# Sheet1.net
KiCad netlist of a schematic drawn in Altium Designer
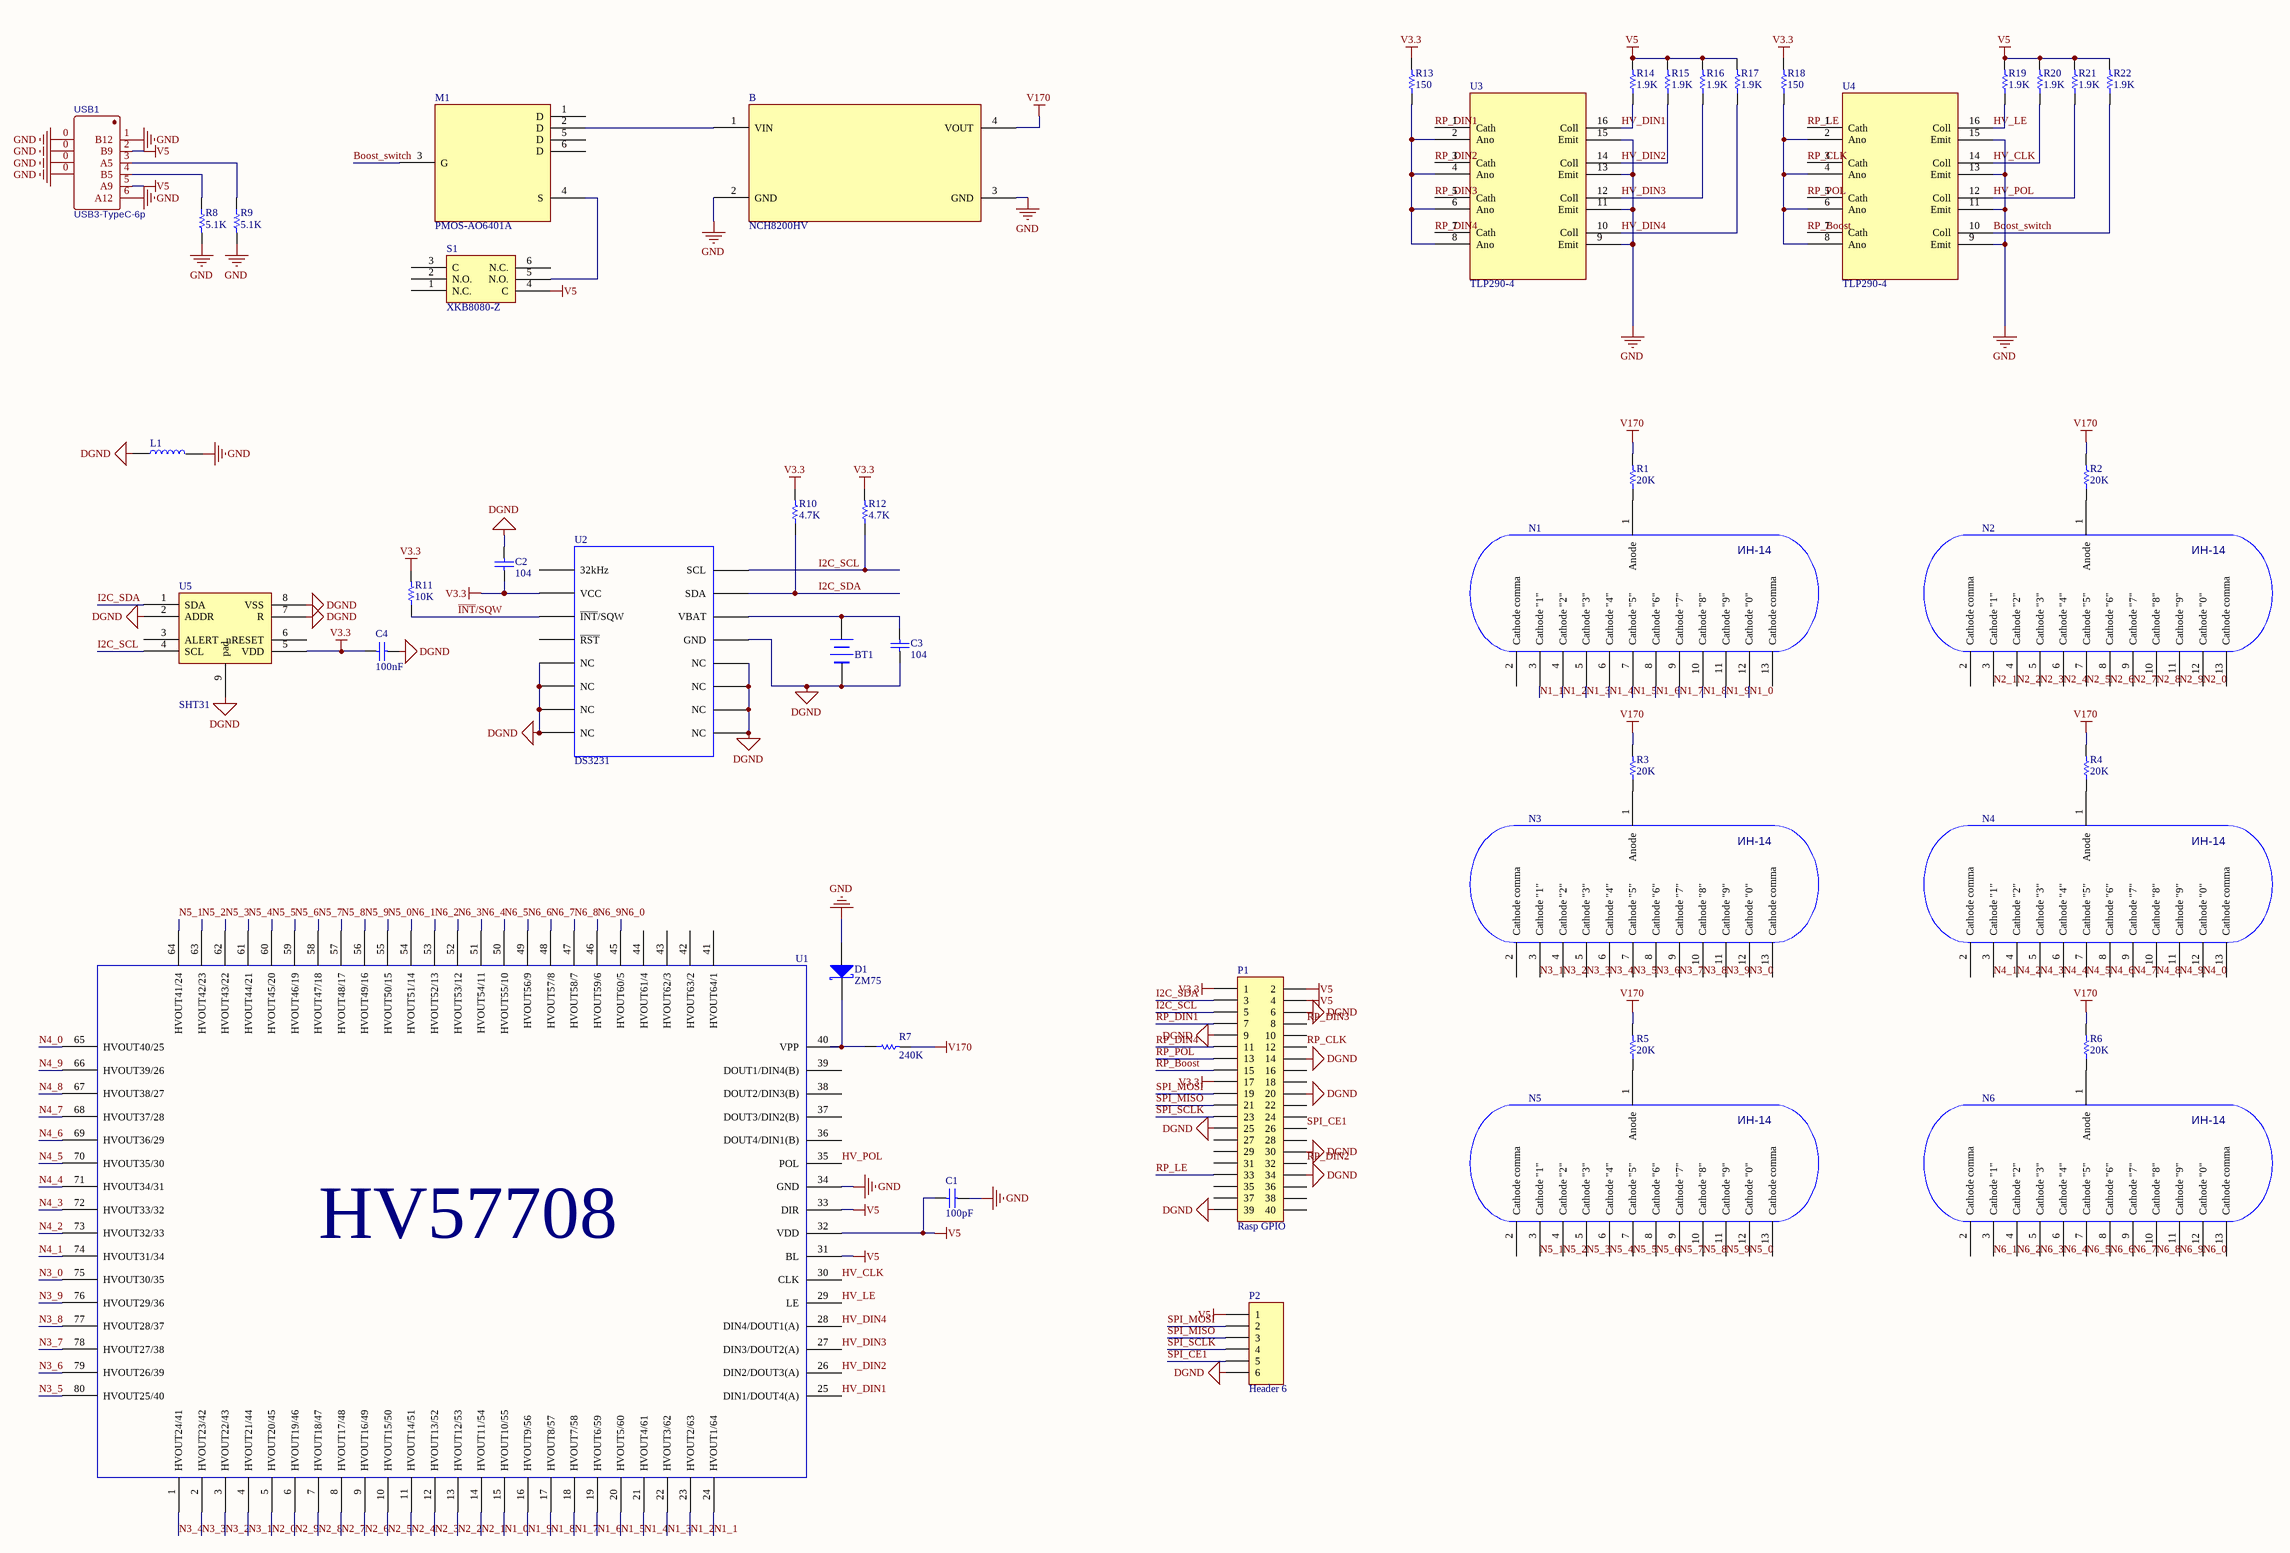
[diagram p0: Sheet1.SchDoc]

(export (version "E")
  (design (tool "Eeschema 10.0.6"))
  (components
    (comp (ref "B")
      (value "NCH8200HV")
      (footprint "NCH8200HV")
      (libsource (lib "Schlib1") (part "NCH8200HV"))
    )
    (comp (ref "BT1") (value "CR1220 holder") (footprint "BAT1220") (libsource (lib "何龙华") (part "BATTERY")))
    (comp (ref "C1")
      (value "100pF")
      (footprint "C0603")
      (description "Capacitor")
      (fields (field (name "Comment") "Cap") (field (name "PUBLISHER") "Altium Limited"))
      (libsource (lib "Miscellaneous Devices") (part "Cap"))
    )
    (comp (ref "C2")
      (value "104")
      (footprint "C0603")
      (description "Capacitor (Semiconductor SIM Model)")
      (fields (field (name "Comment") "Cap Semi") (field (name "PUBLISHER") "Altium Limited"))
      (libsource (lib "何龙华") (part "Cap Semi"))
    )
    (comp (ref "C3")
      (value "104")
      (footprint "C0603")
      (description "Capacitor (Semiconductor SIM Model)")
      (fields (field (name "Comment") "Cap Semi") (field (name "PUBLISHER") "Altium Limited"))
      (libsource (lib "何龙华") (part "Cap Semi"))
    )
    (comp (ref "C4")
      (value "100nF")
      (footprint "C0603")
      (description "Capacitor")
      (fields (field (name "Comment") "Cap") (field (name "PUBLISHER") "Altium Limited"))
      (libsource (lib "Miscellaneous Devices") (part "Cap"))
    )
    (comp (ref "D1")
      (value "ZM75")
      (footprint "LL-34")
      (description "Schottky Rectifier")
      (fields (field (name "PUBLISHER") "Altium Limited"))
      (libsource (lib "Miscellaneous Devices") (part "Diode 11DQ03"))
    )
    (comp (ref "L1") (value "L0") (footprint "0805") (libsource (lib "何龙华") (part "L0")))
    (comp (ref "M1")
      (value "PMOS-AO6401A")
      (footprint "SOT95P250X110-6N")
      (libsource (lib "Schlib1") (part "AO6401A"))
    )
    (comp (ref "N1") (value "ИН-14") (footprint "IN14") (libsource (lib "NIXIEClock_SCHLib") (part "ИН-14")))
    (comp (ref "N2") (value "ИН-14") (footprint "IN14") (libsource (lib "NIXIEClock_SCHLib") (part "ИН-14")))
    (comp (ref "N3") (value "ИН-14") (footprint "IN14") (libsource (lib "NIXIEClock_SCHLib") (part "ИН-14")))
    (comp (ref "N4") (value "ИН-14") (footprint "IN14") (libsource (lib "NIXIEClock_SCHLib") (part "ИН-14")))
    (comp (ref "N5") (value "ИН-14") (footprint "IN14") (libsource (lib "NIXIEClock_SCHLib") (part "ИН-14")))
    (comp (ref "N6") (value "ИН-14") (footprint "IN14") (libsource (lib "NIXIEClock_SCHLib") (part "ИН-14")))
    (comp (ref "P1")
      (value "Rasp GPIO")
      (footprint "HDR2.54-LI-2x20P")
      (description "Header, 20-Pin, Dual row")
      (fields (field (name "PUBLISHER") "Altium Limited"))
      (libsource (lib "Miscellaneous Connectors") (part "Header 20X2"))
    )
    (comp (ref "P2")
      (value "Header 6")
      (footprint "HDR2.54-LI-6P")
      (description "Header, 6-Pin")
      (fields (field (name "PUBLISHER") "Altium Limited"))
      (libsource (lib "Miscellaneous Connectors") (part "Header 6"))
    )
    (comp (ref "R1")
      (value "20K")
      (footprint "R0603")
      (description "Semiconductor Resistor")
      (fields (field (name "Comment") "Res Semi") (field (name "PUBLISHER") "Altium Limited"))
      (libsource (lib "何龙华") (part "Res Semi"))
    )
    (comp (ref "R2")
      (value "20K")
      (footprint "R0603")
      (description "Semiconductor Resistor")
      (fields (field (name "Comment") "Res Semi") (field (name "PUBLISHER") "Altium Limited"))
      (libsource (lib "何龙华") (part "Res Semi"))
    )
    (comp (ref "R3")
      (value "20K")
      (footprint "R0603")
      (description "Semiconductor Resistor")
      (fields (field (name "Comment") "Res Semi") (field (name "PUBLISHER") "Altium Limited"))
      (libsource (lib "何龙华") (part "Res Semi"))
    )
    (comp (ref "R4")
      (value "20K")
      (footprint "R0603")
      (description "Semiconductor Resistor")
      (fields (field (name "Comment") "Res Semi") (field (name "PUBLISHER") "Altium Limited"))
      (libsource (lib "何龙华") (part "Res Semi"))
    )
    (comp (ref "R5")
      (value "20K")
      (footprint "R0603")
      (description "Semiconductor Resistor")
      (fields (field (name "Comment") "Res Semi") (field (name "PUBLISHER") "Altium Limited"))
      (libsource (lib "何龙华") (part "Res Semi"))
    )
    (comp (ref "R6")
      (value "20K")
      (footprint "R0603")
      (description "Semiconductor Resistor")
      (fields (field (name "Comment") "Res Semi") (field (name "PUBLISHER") "Altium Limited"))
      (libsource (lib "何龙华") (part "Res Semi"))
    )
    (comp (ref "R7")
      (value "240K")
      (footprint "R0603")
      (description "Semiconductor Resistor")
      (fields (field (name "Comment") "Res Semi") (field (name "PUBLISHER") "Altium Limited"))
      (libsource (lib "何龙华") (part "Res Semi"))
    )
    (comp (ref "R8")
      (value "5.1K")
      (footprint "R0603")
      (description "Semiconductor Resistor")
      (fields (field (name "Comment") "Res Semi") (field (name "PUBLISHER") "Altium Limited"))
      (libsource (lib "何龙华") (part "Res Semi"))
    )
    (comp (ref "R9")
      (value "5.1K")
      (footprint "R0603")
      (description "Semiconductor Resistor")
      (fields (field (name "Comment") "Res Semi") (field (name "PUBLISHER") "Altium Limited"))
      (libsource (lib "何龙华") (part "Res Semi"))
    )
    (comp (ref "R10")
      (value "4.7K")
      (footprint "R0603")
      (description "Semiconductor Resistor")
      (fields (field (name "Comment") "Res Semi") (field (name "PUBLISHER") "Altium Limited"))
      (libsource (lib "何龙华") (part "Res Semi"))
    )
    (comp (ref "R11")
      (value "10K")
      (footprint "R0603")
      (description "Semiconductor Resistor")
      (fields (field (name "Comment") "Res Semi") (field (name "PUBLISHER") "Altium Limited"))
      (libsource (lib "何龙华") (part "Res Semi"))
    )
    (comp (ref "R12")
      (value "4.7K")
      (footprint "R0603")
      (description "Semiconductor Resistor")
      (fields (field (name "Comment") "Res Semi") (field (name "PUBLISHER") "Altium Limited"))
      (libsource (lib "何龙华") (part "Res Semi"))
    )
    (comp (ref "R13")
      (value "150")
      (footprint "R0603")
      (description "Semiconductor Resistor")
      (fields (field (name "Comment") "Res Semi") (field (name "PUBLISHER") "Altium Limited"))
      (libsource (lib "何龙华") (part "Res Semi"))
    )
    (comp (ref "R14")
      (value "1.9K")
      (footprint "R0603")
      (description "Semiconductor Resistor")
      (fields (field (name "Comment") "Res Semi") (field (name "PUBLISHER") "Altium Limited"))
      (libsource (lib "何龙华") (part "Res Semi"))
    )
    (comp (ref "R15")
      (value "1.9K")
      (footprint "R0603")
      (description "Semiconductor Resistor")
      (fields (field (name "Comment") "Res Semi") (field (name "PUBLISHER") "Altium Limited"))
      (libsource (lib "何龙华") (part "Res Semi"))
    )
    (comp (ref "R16")
      (value "1.9K")
      (footprint "R0603")
      (description "Semiconductor Resistor")
      (fields (field (name "Comment") "Res Semi") (field (name "PUBLISHER") "Altium Limited"))
      (libsource (lib "何龙华") (part "Res Semi"))
    )
    (comp (ref "R17")
      (value "1.9K")
      (footprint "R0603")
      (description "Semiconductor Resistor")
      (fields (field (name "Comment") "Res Semi") (field (name "PUBLISHER") "Altium Limited"))
      (libsource (lib "何龙华") (part "Res Semi"))
    )
    (comp (ref "R18")
      (value "150")
      (footprint "R0603")
      (description "Semiconductor Resistor")
      (fields (field (name "Comment") "Res Semi") (field (name "PUBLISHER") "Altium Limited"))
      (libsource (lib "何龙华") (part "Res Semi"))
    )
    (comp (ref "R19")
      (value "1.9K")
      (footprint "R0603")
      (description "Semiconductor Resistor")
      (fields (field (name "Comment") "Res Semi") (field (name "PUBLISHER") "Altium Limited"))
      (libsource (lib "何龙华") (part "Res Semi"))
    )
    (comp (ref "R20")
      (value "1.9K")
      (footprint "R0603")
      (description "Semiconductor Resistor")
      (fields (field (name "Comment") "Res Semi") (field (name "PUBLISHER") "Altium Limited"))
      (libsource (lib "何龙华") (part "Res Semi"))
    )
    (comp (ref "R21")
      (value "1.9K")
      (footprint "R0603")
      (description "Semiconductor Resistor")
      (fields (field (name "Comment") "Res Semi") (field (name "PUBLISHER") "Altium Limited"))
      (libsource (lib "何龙华") (part "Res Semi"))
    )
    (comp (ref "R22")
      (value "1.9K")
      (footprint "R0603")
      (description "Semiconductor Resistor")
      (fields (field (name "Comment") "Res Semi") (field (name "PUBLISHER") "Altium Limited"))
      (libsource (lib "何龙华") (part "Res Semi"))
    )
    (comp (ref "S1")
      (value "XKB8080-Z")
      (footprint "SW_PVA2EEH21.7NV2")
      (libsource (lib "Schlib1") (part "XKB8080-Z"))
    )
    (comp (ref "U1")
      (value "HV57708")
      (footprint "HV57708PG")
      (libsource (lib "NIXIEClock_SCHLib") (part "HV57708"))
    )
    (comp (ref "U2") (value "DS3231") (footprint "SOP16_75MM") (libsource (lib "NIXIEClock") (part "DS3231")))
    (comp (ref "U3") (value "TLP290-4") (footprint "SO16") (libsource (lib "Schlib1") (part "TLP290-4")))
    (comp (ref "U4") (value "TLP290-4") (footprint "SO16") (libsource (lib "Schlib1") (part "TLP290-4")))
    (comp (ref "U5") (value "SHT31") (footprint "SHT3x-x-P") (libsource (lib "Schlib1") (part "SHT31")))
    (comp (ref "USB1")
      (value "USB3-TypeC-6p")
      (footprint "USB-TYPE-C-SMD6")
      (libsource (lib "type-c-sch") (part "USB3-TypeC-6p"))
    )
  )
  (nets
    (net (code "1") (name "/Boost_switch") (class "Default")
      (node (ref "M1") (pin "3") (pinfunction "G_3") (pintype "passive"))
      (node (ref "R22") (pin "1") (pinfunction "1_1") (pintype "passive"))
      (node (ref "U4") (pin "10") (pinfunction "Coll_10") (pintype "passive"))
    )
    (net (code "2") (name "/HV_CLK") (class "Default")
      (node (ref "R20") (pin "1") (pinfunction "1_1") (pintype "passive"))
      (node (ref "U1") (pin "30") (pinfunction "CLK_30") (pintype "passive"))
      (node (ref "U4") (pin "14") (pinfunction "Coll_14") (pintype "passive"))
    )
    (net (code "3") (name "/HV_DIN1") (class "Default")
      (node (ref "R14") (pin "1") (pinfunction "1_1") (pintype "passive"))
      (node (ref "U1") (pin "25") (pinfunction "DIN1/DOUT4(A)_25") (pintype "passive"))
      (node (ref "U3") (pin "16") (pinfunction "Coll_16") (pintype "passive"))
    )
    (net (code "4") (name "/HV_DIN2") (class "Default")
      (node (ref "R15") (pin "1") (pinfunction "1_1") (pintype "passive"))
      (node (ref "U1") (pin "26") (pinfunction "DIN2/DOUT3(A)_26") (pintype "passive"))
      (node (ref "U3") (pin "14") (pinfunction "Coll_14") (pintype "passive"))
    )
    (net (code "5") (name "/HV_DIN3") (class "Default")
      (node (ref "R16") (pin "1") (pinfunction "1_1") (pintype "passive"))
      (node (ref "U1") (pin "27") (pinfunction "DIN3/DOUT2(A)_27") (pintype "passive"))
      (node (ref "U3") (pin "12") (pinfunction "Coll_12") (pintype "passive"))
    )
    (net (code "6") (name "/HV_DIN4") (class "Default")
      (node (ref "R17") (pin "1") (pinfunction "1_1") (pintype "passive"))
      (node (ref "U1") (pin "28") (pinfunction "DIN4/DOUT1(A)_28") (pintype "passive"))
      (node (ref "U3") (pin "10") (pinfunction "Coll_10") (pintype "passive"))
    )
    (net (code "7") (name "/HV_LE") (class "Default")
      (node (ref "R19") (pin "1") (pinfunction "1_1") (pintype "passive"))
      (node (ref "U1") (pin "29") (pinfunction "LE_29") (pintype "passive"))
      (node (ref "U4") (pin "16") (pinfunction "Coll_16") (pintype "passive"))
    )
    (net (code "8") (name "/HV_POL") (class "Default")
      (node (ref "R21") (pin "1") (pinfunction "1_1") (pintype "passive"))
      (node (ref "U1") (pin "35") (pinfunction "POL_35") (pintype "passive"))
      (node (ref "U4") (pin "12") (pinfunction "Coll_12") (pintype "passive"))
    )
    (net (code "9") (name "/I2C_SCL") (class "Default")
      (node (ref "P1") (pin "5") (pinfunction "5_5") (pintype "passive"))
      (node (ref "R12") (pin "1") (pinfunction "1_1") (pintype "passive"))
      (node (ref "U2") (pin "16") (pinfunction "SCL_16") (pintype "passive"))
      (node (ref "U5") (pin "4") (pinfunction "SCL_4") (pintype "passive"))
    )
    (net (code "10") (name "/I2C_SDA") (class "Default")
      (node (ref "P1") (pin "3") (pinfunction "3_3") (pintype "passive"))
      (node (ref "R10") (pin "1") (pinfunction "1_1") (pintype "passive"))
      (node (ref "U2") (pin "15") (pinfunction "SDA_15") (pintype "passive"))
      (node (ref "U5") (pin "1") (pinfunction "SDA_1") (pintype "passive"))
    )
    (net (code "11") (name "/N1_0") (class "Default")
      (node (ref "N1") (pin "12") (pinfunction "Cathode_\"0\"_12") (pintype "passive"))
      (node (ref "U1") (pin "15") (pinfunction "HVOUT10/55_15") (pintype "passive"))
    )
    (net (code "12") (name "/N1_1") (class "Default")
      (node (ref "N1") (pin "3") (pinfunction "Cathode_\"1\"_3") (pintype "passive"))
      (node (ref "U1") (pin "24") (pinfunction "HVOUT1/64_24") (pintype "passive"))
    )
    (net (code "13") (name "/N1_2") (class "Default")
      (node (ref "N1") (pin "4") (pinfunction "Cathode_\"2\"_4") (pintype "passive"))
      (node (ref "U1") (pin "23") (pinfunction "HVOUT2/63_23") (pintype "passive"))
    )
    (net (code "14") (name "/N1_3") (class "Default")
      (node (ref "N1") (pin "5") (pinfunction "Cathode_\"3\"_5") (pintype "passive"))
      (node (ref "U1") (pin "22") (pinfunction "HVOUT3/62_22") (pintype "passive"))
    )
    (net (code "15") (name "/N1_4") (class "Default")
      (node (ref "N1") (pin "6") (pinfunction "Cathode_\"4\"_6") (pintype "passive"))
      (node (ref "U1") (pin "21") (pinfunction "HVOUT4/61_21") (pintype "passive"))
    )
    (net (code "16") (name "/N1_5") (class "Default")
      (node (ref "N1") (pin "7") (pinfunction "Cathode_\"5\"_7") (pintype "passive"))
      (node (ref "U1") (pin "20") (pinfunction "HVOUT5/60_20") (pintype "passive"))
    )
    (net (code "17") (name "/N1_6") (class "Default")
      (node (ref "N1") (pin "8") (pinfunction "Cathode_\"6\"_8") (pintype "passive"))
      (node (ref "U1") (pin "19") (pinfunction "HVOUT6/59_19") (pintype "passive"))
    )
    (net (code "18") (name "/N1_7") (class "Default")
      (node (ref "N1") (pin "9") (pinfunction "Cathode_\"7\"_9") (pintype "passive"))
      (node (ref "U1") (pin "18") (pinfunction "HVOUT7/58_18") (pintype "passive"))
    )
    (net (code "19") (name "/N1_8") (class "Default")
      (node (ref "N1") (pin "10") (pinfunction "Cathode_\"8\"_10") (pintype "passive"))
      (node (ref "U1") (pin "17") (pinfunction "HVOUT8/57_17") (pintype "passive"))
    )
    (net (code "20") (name "/N1_9") (class "Default")
      (node (ref "N1") (pin "11") (pinfunction "Cathode_\"9\"_11") (pintype "passive"))
      (node (ref "U1") (pin "16") (pinfunction "HVOUT9/56_16") (pintype "passive"))
    )
    (net (code "21") (name "/N2_0") (class "Default")
      (node (ref "N2") (pin "12") (pinfunction "Cathode_\"0\"_12") (pintype "passive"))
      (node (ref "U1") (pin "5") (pinfunction "HVOUT20/45_5") (pintype "passive"))
    )
    (net (code "22") (name "/N2_1") (class "Default")
      (node (ref "N2") (pin "3") (pinfunction "Cathode_\"1\"_3") (pintype "passive"))
      (node (ref "U1") (pin "14") (pinfunction "HVOUT11/54_14") (pintype "passive"))
    )
    (net (code "23") (name "/N2_2") (class "Default")
      (node (ref "N2") (pin "4") (pinfunction "Cathode_\"2\"_4") (pintype "passive"))
      (node (ref "U1") (pin "13") (pinfunction "HVOUT12/53_13") (pintype "passive"))
    )
    (net (code "24") (name "/N2_3") (class "Default")
      (node (ref "N2") (pin "5") (pinfunction "Cathode_\"3\"_5") (pintype "passive"))
      (node (ref "U1") (pin "12") (pinfunction "HVOUT13/52_12") (pintype "passive"))
    )
    (net (code "25") (name "/N2_4") (class "Default")
      (node (ref "N2") (pin "6") (pinfunction "Cathode_\"4\"_6") (pintype "passive"))
      (node (ref "U1") (pin "11") (pinfunction "HVOUT14/51_11") (pintype "passive"))
    )
    (net (code "26") (name "/N2_5") (class "Default")
      (node (ref "N2") (pin "7") (pinfunction "Cathode_\"5\"_7") (pintype "passive"))
      (node (ref "U1") (pin "10") (pinfunction "HVOUT15/50_10") (pintype "passive"))
    )
    (net (code "27") (name "/N2_6") (class "Default")
      (node (ref "N2") (pin "8") (pinfunction "Cathode_\"6\"_8") (pintype "passive"))
      (node (ref "U1") (pin "9") (pinfunction "HVOUT16/49_9") (pintype "passive"))
    )
    (net (code "28") (name "/N2_7") (class "Default")
      (node (ref "N2") (pin "9") (pinfunction "Cathode_\"7\"_9") (pintype "passive"))
      (node (ref "U1") (pin "8") (pinfunction "HVOUT17/48_8") (pintype "passive"))
    )
    (net (code "29") (name "/N2_8") (class "Default")
      (node (ref "N2") (pin "10") (pinfunction "Cathode_\"8\"_10") (pintype "passive"))
      (node (ref "U1") (pin "7") (pinfunction "HVOUT18/47_7") (pintype "passive"))
    )
    (net (code "30") (name "/N2_9") (class "Default")
      (node (ref "N2") (pin "11") (pinfunction "Cathode_\"9\"_11") (pintype "passive"))
      (node (ref "U1") (pin "6") (pinfunction "HVOUT19/46_6") (pintype "passive"))
    )
    (net (code "31") (name "/N3_0") (class "Default")
      (node (ref "N3") (pin "12") (pinfunction "Cathode_\"0\"_12") (pintype "passive"))
      (node (ref "U1") (pin "75") (pinfunction "HVOUT30/35_75") (pintype "passive"))
    )
    (net (code "32") (name "/N3_1") (class "Default")
      (node (ref "N3") (pin "3") (pinfunction "Cathode_\"1\"_3") (pintype "passive"))
      (node (ref "U1") (pin "4") (pinfunction "HVOUT21/44_4") (pintype "passive"))
    )
    (net (code "33") (name "/N3_2") (class "Default")
      (node (ref "N3") (pin "4") (pinfunction "Cathode_\"2\"_4") (pintype "passive"))
      (node (ref "U1") (pin "3") (pinfunction "HVOUT22/43_3") (pintype "passive"))
    )
    (net (code "34") (name "/N3_3") (class "Default")
      (node (ref "N3") (pin "5") (pinfunction "Cathode_\"3\"_5") (pintype "passive"))
      (node (ref "U1") (pin "2") (pinfunction "HVOUT23/42_2") (pintype "passive"))
    )
    (net (code "35") (name "/N3_4") (class "Default")
      (node (ref "N3") (pin "6") (pinfunction "Cathode_\"4\"_6") (pintype "passive"))
      (node (ref "U1") (pin "1") (pinfunction "HVOUT24/41_1") (pintype "passive"))
    )
    (net (code "36") (name "/N3_5") (class "Default")
      (node (ref "N3") (pin "7") (pinfunction "Cathode_\"5\"_7") (pintype "passive"))
      (node (ref "U1") (pin "80") (pinfunction "HVOUT25/40_80") (pintype "passive"))
    )
    (net (code "37") (name "/N3_6") (class "Default")
      (node (ref "N3") (pin "8") (pinfunction "Cathode_\"6\"_8") (pintype "passive"))
      (node (ref "U1") (pin "79") (pinfunction "HVOUT26/39_79") (pintype "passive"))
    )
    (net (code "38") (name "/N3_7") (class "Default")
      (node (ref "N3") (pin "9") (pinfunction "Cathode_\"7\"_9") (pintype "passive"))
      (node (ref "U1") (pin "78") (pinfunction "HVOUT27/38_78") (pintype "passive"))
    )
    (net (code "39") (name "/N3_8") (class "Default")
      (node (ref "N3") (pin "10") (pinfunction "Cathode_\"8\"_10") (pintype "passive"))
      (node (ref "U1") (pin "77") (pinfunction "HVOUT28/37_77") (pintype "passive"))
    )
    (net (code "40") (name "/N3_9") (class "Default")
      (node (ref "N3") (pin "11") (pinfunction "Cathode_\"9\"_11") (pintype "passive"))
      (node (ref "U1") (pin "76") (pinfunction "HVOUT29/36_76") (pintype "passive"))
    )
    (net (code "41") (name "/N4_0") (class "Default")
      (node (ref "N4") (pin "12") (pinfunction "Cathode_\"0\"_12") (pintype "passive"))
      (node (ref "U1") (pin "65") (pinfunction "HVOUT40/25_65") (pintype "passive"))
    )
    (net (code "42") (name "/N4_1") (class "Default")
      (node (ref "N4") (pin "3") (pinfunction "Cathode_\"1\"_3") (pintype "passive"))
      (node (ref "U1") (pin "74") (pinfunction "HVOUT31/34_74") (pintype "passive"))
    )
    (net (code "43") (name "/N4_2") (class "Default")
      (node (ref "N4") (pin "4") (pinfunction "Cathode_\"2\"_4") (pintype "passive"))
      (node (ref "U1") (pin "73") (pinfunction "HVOUT32/33_73") (pintype "passive"))
    )
    (net (code "44") (name "/N4_3") (class "Default")
      (node (ref "N4") (pin "5") (pinfunction "Cathode_\"3\"_5") (pintype "passive"))
      (node (ref "U1") (pin "72") (pinfunction "HVOUT33/32_72") (pintype "passive"))
    )
    (net (code "45") (name "/N4_4") (class "Default")
      (node (ref "N4") (pin "6") (pinfunction "Cathode_\"4\"_6") (pintype "passive"))
      (node (ref "U1") (pin "71") (pinfunction "HVOUT34/31_71") (pintype "passive"))
    )
    (net (code "46") (name "/N4_5") (class "Default")
      (node (ref "N4") (pin "7") (pinfunction "Cathode_\"5\"_7") (pintype "passive"))
      (node (ref "U1") (pin "70") (pinfunction "HVOUT35/30_70") (pintype "passive"))
    )
    (net (code "47") (name "/N4_6") (class "Default")
      (node (ref "N4") (pin "8") (pinfunction "Cathode_\"6\"_8") (pintype "passive"))
      (node (ref "U1") (pin "69") (pinfunction "HVOUT36/29_69") (pintype "passive"))
    )
    (net (code "48") (name "/N4_7") (class "Default")
      (node (ref "N4") (pin "9") (pinfunction "Cathode_\"7\"_9") (pintype "passive"))
      (node (ref "U1") (pin "68") (pinfunction "HVOUT37/28_68") (pintype "passive"))
    )
    (net (code "49") (name "/N4_8") (class "Default")
      (node (ref "N4") (pin "10") (pinfunction "Cathode_\"8\"_10") (pintype "passive"))
      (node (ref "U1") (pin "67") (pinfunction "HVOUT38/27_67") (pintype "passive"))
    )
    (net (code "50") (name "/N4_9") (class "Default")
      (node (ref "N4") (pin "11") (pinfunction "Cathode_\"9\"_11") (pintype "passive"))
      (node (ref "U1") (pin "66") (pinfunction "HVOUT39/26_66") (pintype "passive"))
    )
    (net (code "51") (name "/N5_0") (class "Default")
      (node (ref "N5") (pin "12") (pinfunction "Cathode_\"0\"_12") (pintype "passive"))
      (node (ref "U1") (pin "55") (pinfunction "HVOUT50/15_55") (pintype "passive"))
    )
    (net (code "52") (name "/N5_1") (class "Default")
      (node (ref "N5") (pin "3") (pinfunction "Cathode_\"1\"_3") (pintype "passive"))
      (node (ref "U1") (pin "64") (pinfunction "HVOUT41/24_64") (pintype "passive"))
    )
    (net (code "53") (name "/N5_2") (class "Default")
      (node (ref "N5") (pin "4") (pinfunction "Cathode_\"2\"_4") (pintype "passive"))
      (node (ref "U1") (pin "63") (pinfunction "HVOUT42/23_63") (pintype "passive"))
    )
    (net (code "54") (name "/N5_3") (class "Default")
      (node (ref "N5") (pin "5") (pinfunction "Cathode_\"3\"_5") (pintype "passive"))
      (node (ref "U1") (pin "62") (pinfunction "HVOUT43/22_62") (pintype "passive"))
    )
    (net (code "55") (name "/N5_4") (class "Default")
      (node (ref "N5") (pin "6") (pinfunction "Cathode_\"4\"_6") (pintype "passive"))
      (node (ref "U1") (pin "61") (pinfunction "HVOUT44/21_61") (pintype "passive"))
    )
    (net (code "56") (name "/N5_5") (class "Default")
      (node (ref "N5") (pin "7") (pinfunction "Cathode_\"5\"_7") (pintype "passive"))
      (node (ref "U1") (pin "60") (pinfunction "HVOUT45/20_60") (pintype "passive"))
    )
    (net (code "57") (name "/N5_6") (class "Default")
      (node (ref "N5") (pin "8") (pinfunction "Cathode_\"6\"_8") (pintype "passive"))
      (node (ref "U1") (pin "59") (pinfunction "HVOUT46/19_59") (pintype "passive"))
    )
    (net (code "58") (name "/N5_7") (class "Default")
      (node (ref "N5") (pin "9") (pinfunction "Cathode_\"7\"_9") (pintype "passive"))
      (node (ref "U1") (pin "58") (pinfunction "HVOUT47/18_58") (pintype "passive"))
    )
    (net (code "59") (name "/N5_8") (class "Default")
      (node (ref "N5") (pin "10") (pinfunction "Cathode_\"8\"_10") (pintype "passive"))
      (node (ref "U1") (pin "57") (pinfunction "HVOUT48/17_57") (pintype "passive"))
    )
    (net (code "60") (name "/N5_9") (class "Default")
      (node (ref "N5") (pin "11") (pinfunction "Cathode_\"9\"_11") (pintype "passive"))
      (node (ref "U1") (pin "56") (pinfunction "HVOUT49/16_56") (pintype "passive"))
    )
    (net (code "61") (name "/N6_0") (class "Default")
      (node (ref "N6") (pin "12") (pinfunction "Cathode_\"0\"_12") (pintype "passive"))
      (node (ref "U1") (pin "45") (pinfunction "HVOUT60/5_45") (pintype "passive"))
    )
    (net (code "62") (name "/N6_1") (class "Default")
      (node (ref "N6") (pin "3") (pinfunction "Cathode_\"1\"_3") (pintype "passive"))
      (node (ref "U1") (pin "54") (pinfunction "HVOUT51/14_54") (pintype "passive"))
    )
    (net (code "63") (name "/N6_2") (class "Default")
      (node (ref "N6") (pin "4") (pinfunction "Cathode_\"2\"_4") (pintype "passive"))
      (node (ref "U1") (pin "53") (pinfunction "HVOUT52/13_53") (pintype "passive"))
    )
    (net (code "64") (name "/N6_3") (class "Default")
      (node (ref "N6") (pin "5") (pinfunction "Cathode_\"3\"_5") (pintype "passive"))
      (node (ref "U1") (pin "52") (pinfunction "HVOUT53/12_52") (pintype "passive"))
    )
    (net (code "65") (name "/N6_4") (class "Default")
      (node (ref "N6") (pin "6") (pinfunction "Cathode_\"4\"_6") (pintype "passive"))
      (node (ref "U1") (pin "51") (pinfunction "HVOUT54/11_51") (pintype "passive"))
    )
    (net (code "66") (name "/N6_5") (class "Default")
      (node (ref "N6") (pin "7") (pinfunction "Cathode_\"5\"_7") (pintype "passive"))
      (node (ref "U1") (pin "50") (pinfunction "HVOUT55/10_50") (pintype "passive"))
    )
    (net (code "67") (name "/N6_6") (class "Default")
      (node (ref "N6") (pin "8") (pinfunction "Cathode_\"6\"_8") (pintype "passive"))
      (node (ref "U1") (pin "49") (pinfunction "HVOUT56/9_49") (pintype "passive"))
    )
    (net (code "68") (name "/N6_7") (class "Default")
      (node (ref "N6") (pin "9") (pinfunction "Cathode_\"7\"_9") (pintype "passive"))
      (node (ref "U1") (pin "48") (pinfunction "HVOUT57/8_48") (pintype "passive"))
    )
    (net (code "69") (name "/N6_8") (class "Default")
      (node (ref "N6") (pin "10") (pinfunction "Cathode_\"8\"_10") (pintype "passive"))
      (node (ref "U1") (pin "47") (pinfunction "HVOUT58/7_47") (pintype "passive"))
    )
    (net (code "70") (name "/N6_9") (class "Default")
      (node (ref "N6") (pin "11") (pinfunction "Cathode_\"9\"_11") (pintype "passive"))
      (node (ref "U1") (pin "46") (pinfunction "HVOUT59/6_46") (pintype "passive"))
    )
    (net (code "71") (name "/RP_Boost") (class "Default")
      (node (ref "P1") (pin "15") (pinfunction "15_15") (pintype "passive"))
      (node (ref "U4") (pin "7") (pinfunction "Cath_7") (pintype "passive"))
    )
    (net (code "72") (name "/RP_CLK") (class "Default")
      (node (ref "P1") (pin "12") (pinfunction "12_12") (pintype "passive"))
      (node (ref "U4") (pin "3") (pinfunction "Cath_3") (pintype "passive"))
    )
    (net (code "73") (name "/RP_DIN1") (class "Default")
      (node (ref "P1") (pin "7") (pinfunction "7_7") (pintype "passive"))
      (node (ref "U3") (pin "1") (pinfunction "Cath_1") (pintype "passive"))
    )
    (net (code "74") (name "/RP_DIN2") (class "Default")
      (node (ref "P1") (pin "32") (pinfunction "32_32") (pintype "passive"))
      (node (ref "U3") (pin "3") (pinfunction "Cath_3") (pintype "passive"))
    )
    (net (code "75") (name "/RP_DIN3") (class "Default")
      (node (ref "P1") (pin "8") (pinfunction "8_8") (pintype "passive"))
      (node (ref "U3") (pin "5") (pinfunction "Cath_5") (pintype "passive"))
    )
    (net (code "76") (name "/RP_DIN4") (class "Default")
      (node (ref "P1") (pin "11") (pinfunction "11_11") (pintype "passive"))
      (node (ref "U3") (pin "7") (pinfunction "Cath_7") (pintype "passive"))
    )
    (net (code "77") (name "/RP_LE") (class "Default")
      (node (ref "P1") (pin "33") (pinfunction "33_33") (pintype "passive"))
      (node (ref "U4") (pin "1") (pinfunction "Cath_1") (pintype "passive"))
    )
    (net (code "78") (name "/RP_POL") (class "Default")
      (node (ref "P1") (pin "13") (pinfunction "13_13") (pintype "passive"))
      (node (ref "U4") (pin "5") (pinfunction "Cath_5") (pintype "passive"))
    )
    (net (code "79") (name "/SPI_CE1") (class "Default")
      (node (ref "P1") (pin "26") (pinfunction "26_26") (pintype "passive"))
      (node (ref "P2") (pin "5") (pinfunction "5_5") (pintype "passive"))
    )
    (net (code "80") (name "/SPI_MISO") (class "Default")
      (node (ref "P1") (pin "21") (pinfunction "21_21") (pintype "passive"))
      (node (ref "P2") (pin "3") (pinfunction "3_3") (pintype "passive"))
    )
    (net (code "81") (name "/SPI_MOSI") (class "Default")
      (node (ref "P1") (pin "19") (pinfunction "19_19") (pintype "passive"))
      (node (ref "P2") (pin "2") (pinfunction "2_2") (pintype "passive"))
    )
    (net (code "82") (name "/SPI_SCLK") (class "Default")
      (node (ref "P1") (pin "23") (pinfunction "23_23") (pintype "passive"))
      (node (ref "P2") (pin "4") (pinfunction "4_4") (pintype "passive"))
    )
    (net (code "83") (name "/~{INT}{slash}SQW") (class "Default")
      (node (ref "R11") (pin "1") (pinfunction "1_1") (pintype "passive"))
      (node (ref "U2") (pin "3") (pinfunction "~{INT}/SQW_3") (pintype "passive"))
    )
    (net (code "84") (name "DGND") (class "Default")
      (node (ref "BT1") (pin "2") (pinfunction "-_2") (pintype "passive"))
      (node (ref "C2") (pin "2") (pinfunction "2_2") (pintype "passive"))
      (node (ref "C3") (pin "1") (pinfunction "1_1") (pintype "passive"))
      (node (ref "C4") (pin "1") (pinfunction "1_1") (pintype "passive"))
      (node (ref "L1") (pin "1") (pinfunction "1_1") (pintype "passive"))
      (node (ref "P1") (pin "14") (pinfunction "14_14") (pintype "passive"))
      (node (ref "P1") (pin "20") (pinfunction "20_20") (pintype "passive"))
      (node (ref "P1") (pin "25") (pinfunction "25_25") (pintype "passive"))
      (node (ref "P1") (pin "30") (pinfunction "30_30") (pintype "passive"))
      (node (ref "P1") (pin "34") (pinfunction "34_34") (pintype "passive"))
      (node (ref "P1") (pin "39") (pinfunction "39_39") (pintype "passive"))
      (node (ref "P1") (pin "6") (pinfunction "6_6") (pintype "passive"))
      (node (ref "P1") (pin "9") (pinfunction "9_9") (pintype "passive"))
      (node (ref "P2") (pin "6") (pinfunction "6_6") (pintype "passive"))
      (node (ref "U2") (pin "10") (pinfunction "NC_10") (pintype "passive"))
      (node (ref "U2") (pin "11") (pinfunction "NC_11") (pintype "passive"))
      (node (ref "U2") (pin "12") (pinfunction "NC_12") (pintype "passive"))
      (node (ref "U2") (pin "13") (pinfunction "GND_13") (pintype "passive"))
      (node (ref "U2") (pin "5") (pinfunction "NC_5") (pintype "passive"))
      (node (ref "U2") (pin "6") (pinfunction "NC_6") (pintype "passive"))
      (node (ref "U2") (pin "7") (pinfunction "NC_7") (pintype "passive"))
      (node (ref "U2") (pin "8") (pinfunction "NC_8") (pintype "passive"))
      (node (ref "U2") (pin "9") (pinfunction "NC_9") (pintype "passive"))
      (node (ref "U5") (pin "2") (pinfunction "ADDR_2") (pintype "passive"))
      (node (ref "U5") (pin "7") (pinfunction "R_7") (pintype "passive"))
      (node (ref "U5") (pin "8") (pinfunction "VSS_8") (pintype "passive"))
      (node (ref "U5") (pin "9") (pinfunction "pad_9") (pintype "passive"))
    )
    (net (code "85") (name "GND") (class "Default")
      (node (ref "B") (pin "2") (pinfunction "GND_2") (pintype "passive"))
      (node (ref "B") (pin "3") (pinfunction "GND_3") (pintype "passive"))
      (node (ref "C1") (pin "1") (pinfunction "1_1") (pintype "passive"))
      (node (ref "D1") (pin "1") (pinfunction "A_1") (pintype "passive"))
      (node (ref "L1") (pin "2") (pinfunction "2_2") (pintype "passive"))
      (node (ref "R8") (pin "2") (pinfunction "2_2") (pintype "passive"))
      (node (ref "R9") (pin "2") (pinfunction "2_2") (pintype "passive"))
      (node (ref "U1") (pin "34") (pinfunction "GND_34") (pintype "passive"))
      (node (ref "U3") (pin "11") (pinfunction "Emit_11") (pintype "passive"))
      (node (ref "U3") (pin "13") (pinfunction "Emit_13") (pintype "passive"))
      (node (ref "U3") (pin "15") (pinfunction "Emit_15") (pintype "passive"))
      (node (ref "U3") (pin "9") (pinfunction "Emit_9") (pintype "passive"))
      (node (ref "U4") (pin "11") (pinfunction "Emit_11") (pintype "passive"))
      (node (ref "U4") (pin "13") (pinfunction "Emit_13") (pintype "passive"))
      (node (ref "U4") (pin "15") (pinfunction "Emit_15") (pintype "passive"))
      (node (ref "U4") (pin "9") (pinfunction "Emit_9") (pintype "passive"))
      (node (ref "USB1") (pin "0") (pinfunction "0_0") (pintype "passive"))
      (node (ref "USB1") (pin "1") (pinfunction "B12_1") (pintype "passive"))
      (node (ref "USB1") (pin "6") (pinfunction "A12_6") (pintype "passive"))
    )
    (net (code "86") (name "Net-(B-VIN)") (class "Default")
      (node (ref "B") (pin "1") (pinfunction "VIN_1") (pintype "passive"))
      (node (ref "M1") (pin "2") (pinfunction "D_2") (pintype "passive"))
    )
    (net (code "87") (name "Net-(BT1-+)") (class "Default")
      (node (ref "BT1") (pin "1") (pinfunction "+_1") (pintype "passive"))
      (node (ref "C3") (pin "2") (pinfunction "2_2") (pintype "passive"))
      (node (ref "U2") (pin "14") (pinfunction "VBAT_14") (pintype "passive"))
    )
    (net (code "88") (name "Net-(D1-K)") (class "Default")
      (node (ref "D1") (pin "2") (pinfunction "K_2") (pintype "passive"))
      (node (ref "R7") (pin "1") (pinfunction "1_1") (pintype "passive"))
      (node (ref "U1") (pin "40") (pinfunction "VPP_40") (pintype "passive"))
    )
    (net (code "89") (name "Net-(M1-S)") (class "Default")
      (node (ref "M1") (pin "4") (pinfunction "S_4") (pintype "passive"))
      (node (ref "S1") (pin "5") (pinfunction "N.O._5") (pintype "passive"))
    )
    (net (code "90") (name "Net-(N1-Anode)") (class "Default")
      (node (ref "N1") (pin "1") (pinfunction "Anode_1") (pintype "passive"))
      (node (ref "R1") (pin "1") (pinfunction "1_1") (pintype "passive"))
    )
    (net (code "91") (name "Net-(N2-Anode)") (class "Default")
      (node (ref "N2") (pin "1") (pinfunction "Anode_1") (pintype "passive"))
      (node (ref "R2") (pin "1") (pinfunction "1_1") (pintype "passive"))
    )
    (net (code "92") (name "Net-(N3-Anode)") (class "Default")
      (node (ref "N3") (pin "1") (pinfunction "Anode_1") (pintype "passive"))
      (node (ref "R3") (pin "1") (pinfunction "1_1") (pintype "passive"))
    )
    (net (code "93") (name "Net-(N4-Anode)") (class "Default")
      (node (ref "N4") (pin "1") (pinfunction "Anode_1") (pintype "passive"))
      (node (ref "R4") (pin "1") (pinfunction "1_1") (pintype "passive"))
    )
    (net (code "94") (name "Net-(N5-Anode)") (class "Default")
      (node (ref "N5") (pin "1") (pinfunction "Anode_1") (pintype "passive"))
      (node (ref "R5") (pin "1") (pinfunction "1_1") (pintype "passive"))
    )
    (net (code "95") (name "Net-(N6-Anode)") (class "Default")
      (node (ref "N6") (pin "1") (pinfunction "Anode_1") (pintype "passive"))
      (node (ref "R6") (pin "1") (pinfunction "1_1") (pintype "passive"))
    )
    (net (code "96") (name "Net-(R13-Pad1)") (class "Default")
      (node (ref "R13") (pin "1") (pinfunction "1_1") (pintype "passive"))
      (node (ref "U3") (pin "2") (pinfunction "Ano_2") (pintype "passive"))
      (node (ref "U3") (pin "4") (pinfunction "Ano_4") (pintype "passive"))
      (node (ref "U3") (pin "6") (pinfunction "Ano_6") (pintype "passive"))
      (node (ref "U3") (pin "8") (pinfunction "Ano_8") (pintype "passive"))
    )
    (net (code "97") (name "Net-(R18-Pad1)") (class "Default")
      (node (ref "R18") (pin "1") (pinfunction "1_1") (pintype "passive"))
      (node (ref "U4") (pin "2") (pinfunction "Ano_2") (pintype "passive"))
      (node (ref "U4") (pin "4") (pinfunction "Ano_4") (pintype "passive"))
      (node (ref "U4") (pin "6") (pinfunction "Ano_6") (pintype "passive"))
      (node (ref "U4") (pin "8") (pinfunction "Ano_8") (pintype "passive"))
    )
    (net (code "98") (name "Net-(USB1-A5)") (class "Default")
      (node (ref "R9") (pin "1") (pinfunction "1_1") (pintype "passive"))
      (node (ref "USB1") (pin "3") (pinfunction "A5_3") (pintype "passive"))
    )
    (net (code "99") (name "Net-(USB1-B5)") (class "Default")
      (node (ref "R8") (pin "1") (pinfunction "1_1") (pintype "passive"))
      (node (ref "USB1") (pin "4") (pinfunction "B5_4") (pintype "passive"))
    )
    (net (code "100") (name "V3.3") (class "Default")
      (node (ref "C2") (pin "1") (pinfunction "1_1") (pintype "passive"))
      (node (ref "C4") (pin "2") (pinfunction "2_2") (pintype "passive"))
      (node (ref "P1") (pin "1") (pinfunction "1_1") (pintype "passive"))
      (node (ref "P1") (pin "17") (pinfunction "17_17") (pintype "passive"))
      (node (ref "R10") (pin "2") (pinfunction "2_2") (pintype "passive"))
      (node (ref "R11") (pin "2") (pinfunction "2_2") (pintype "passive"))
      (node (ref "R12") (pin "2") (pinfunction "2_2") (pintype "passive"))
      (node (ref "R13") (pin "2") (pinfunction "2_2") (pintype "passive"))
      (node (ref "R18") (pin "2") (pinfunction "2_2") (pintype "passive"))
      (node (ref "U2") (pin "2") (pinfunction "VCC_2") (pintype "passive"))
      (node (ref "U5") (pin "5") (pinfunction "VDD_5") (pintype "passive"))
    )
    (net (code "101") (name "V5") (class "Default")
      (node (ref "C1") (pin "2") (pinfunction "2_2") (pintype "passive"))
      (node (ref "P1") (pin "2") (pinfunction "2_2") (pintype "passive"))
      (node (ref "P1") (pin "4") (pinfunction "4_4") (pintype "passive"))
      (node (ref "P2") (pin "1") (pinfunction "1_1") (pintype "passive"))
      (node (ref "R14") (pin "2") (pinfunction "2_2") (pintype "passive"))
      (node (ref "R15") (pin "2") (pinfunction "2_2") (pintype "passive"))
      (node (ref "R16") (pin "2") (pinfunction "2_2") (pintype "passive"))
      (node (ref "R17") (pin "2") (pinfunction "2_2") (pintype "passive"))
      (node (ref "R19") (pin "2") (pinfunction "2_2") (pintype "passive"))
      (node (ref "R20") (pin "2") (pinfunction "2_2") (pintype "passive"))
      (node (ref "R21") (pin "2") (pinfunction "2_2") (pintype "passive"))
      (node (ref "R22") (pin "2") (pinfunction "2_2") (pintype "passive"))
      (node (ref "S1") (pin "4") (pinfunction "C_4") (pintype "passive"))
      (node (ref "U1") (pin "31") (pinfunction "BL_31") (pintype "passive"))
      (node (ref "U1") (pin "32") (pinfunction "VDD_32") (pintype "passive"))
      (node (ref "U1") (pin "33") (pinfunction "DIR_33") (pintype "passive"))
      (node (ref "USB1") (pin "2") (pinfunction "B9_2") (pintype "passive"))
      (node (ref "USB1") (pin "5") (pinfunction "A9_5") (pintype "passive"))
    )
    (net (code "102") (name "V170") (class "Default")
      (node (ref "B") (pin "4") (pinfunction "VOUT_4") (pintype "passive"))
      (node (ref "R1") (pin "2") (pinfunction "2_2") (pintype "passive"))
      (node (ref "R2") (pin "2") (pinfunction "2_2") (pintype "passive"))
      (node (ref "R3") (pin "2") (pinfunction "2_2") (pintype "passive"))
      (node (ref "R4") (pin "2") (pinfunction "2_2") (pintype "passive"))
      (node (ref "R5") (pin "2") (pinfunction "2_2") (pintype "passive"))
      (node (ref "R6") (pin "2") (pinfunction "2_2") (pintype "passive"))
      (node (ref "R7") (pin "2") (pinfunction "2_2") (pintype "passive"))
    )
    (net (code "103") (name "unconnected-(M1-D-Pad1)") (class "Default")
      (node (ref "M1") (pin "1") (pinfunction "D_1") (pintype "passive"))
    )
    (net (code "104") (name "unconnected-(M1-D-Pad5)") (class "Default")
      (node (ref "M1") (pin "5") (pinfunction "D_5") (pintype "passive"))
    )
    (net (code "105") (name "unconnected-(M1-D-Pad6)") (class "Default")
      (node (ref "M1") (pin "6") (pinfunction "D_6") (pintype "passive"))
    )
    (net (code "106") (name "unconnected-(N1-Cathode_comma-Pad2)") (class "Default")
      (node (ref "N1") (pin "2") (pinfunction "Cathode_comma_2") (pintype "passive"))
    )
    (net (code "107") (name "unconnected-(N1-Cathode_comma-Pad13)") (class "Default")
      (node (ref "N1") (pin "13") (pinfunction "Cathode_comma_13") (pintype "passive"))
    )
    (net (code "108") (name "unconnected-(N2-Cathode_comma-Pad2)") (class "Default")
      (node (ref "N2") (pin "2") (pinfunction "Cathode_comma_2") (pintype "passive"))
    )
    (net (code "109") (name "unconnected-(N2-Cathode_comma-Pad13)") (class "Default")
      (node (ref "N2") (pin "13") (pinfunction "Cathode_comma_13") (pintype "passive"))
    )
    (net (code "110") (name "unconnected-(N3-Cathode_comma-Pad2)") (class "Default")
      (node (ref "N3") (pin "2") (pinfunction "Cathode_comma_2") (pintype "passive"))
    )
    (net (code "111") (name "unconnected-(N3-Cathode_comma-Pad13)") (class "Default")
      (node (ref "N3") (pin "13") (pinfunction "Cathode_comma_13") (pintype "passive"))
    )
    (net (code "112") (name "unconnected-(N4-Cathode_comma-Pad2)") (class "Default")
      (node (ref "N4") (pin "2") (pinfunction "Cathode_comma_2") (pintype "passive"))
    )
    (net (code "113") (name "unconnected-(N4-Cathode_comma-Pad13)") (class "Default")
      (node (ref "N4") (pin "13") (pinfunction "Cathode_comma_13") (pintype "passive"))
    )
    (net (code "114") (name "unconnected-(N5-Cathode_comma-Pad2)") (class "Default")
      (node (ref "N5") (pin "2") (pinfunction "Cathode_comma_2") (pintype "passive"))
    )
    (net (code "115") (name "unconnected-(N5-Cathode_comma-Pad13)") (class "Default")
      (node (ref "N5") (pin "13") (pinfunction "Cathode_comma_13") (pintype "passive"))
    )
    (net (code "116") (name "unconnected-(N6-Cathode_comma-Pad2)") (class "Default")
      (node (ref "N6") (pin "2") (pinfunction "Cathode_comma_2") (pintype "passive"))
    )
    (net (code "117") (name "unconnected-(N6-Cathode_comma-Pad13)") (class "Default")
      (node (ref "N6") (pin "13") (pinfunction "Cathode_comma_13") (pintype "passive"))
    )
    (net (code "118") (name "unconnected-(P1-Pad10)") (class "Default")
      (node (ref "P1") (pin "10") (pinfunction "10_10") (pintype "passive"))
    )
    (net (code "119") (name "unconnected-(P1-Pad16)") (class "Default")
      (node (ref "P1") (pin "16") (pinfunction "16_16") (pintype "passive"))
    )
    (net (code "120") (name "unconnected-(P1-Pad18)") (class "Default")
      (node (ref "P1") (pin "18") (pinfunction "18_18") (pintype "passive"))
    )
    (net (code "121") (name "unconnected-(P1-Pad22)") (class "Default")
      (node (ref "P1") (pin "22") (pinfunction "22_22") (pintype "passive"))
    )
    (net (code "122") (name "unconnected-(P1-Pad24)") (class "Default")
      (node (ref "P1") (pin "24") (pinfunction "24_24") (pintype "passive"))
    )
    (net (code "123") (name "unconnected-(P1-Pad27)") (class "Default")
      (node (ref "P1") (pin "27") (pinfunction "27_27") (pintype "passive"))
    )
    (net (code "124") (name "unconnected-(P1-Pad28)") (class "Default")
      (node (ref "P1") (pin "28") (pinfunction "28_28") (pintype "passive"))
    )
    (net (code "125") (name "unconnected-(P1-Pad29)") (class "Default")
      (node (ref "P1") (pin "29") (pinfunction "29_29") (pintype "passive"))
    )
    (net (code "126") (name "unconnected-(P1-Pad31)") (class "Default")
      (node (ref "P1") (pin "31") (pinfunction "31_31") (pintype "passive"))
    )
    (net (code "127") (name "unconnected-(P1-Pad35)") (class "Default")
      (node (ref "P1") (pin "35") (pinfunction "35_35") (pintype "passive"))
    )
    (net (code "128") (name "unconnected-(P1-Pad36)") (class "Default")
      (node (ref "P1") (pin "36") (pinfunction "36_36") (pintype "passive"))
    )
    (net (code "129") (name "unconnected-(P1-Pad37)") (class "Default")
      (node (ref "P1") (pin "37") (pinfunction "37_37") (pintype "passive"))
    )
    (net (code "130") (name "unconnected-(P1-Pad38)") (class "Default")
      (node (ref "P1") (pin "38") (pinfunction "38_38") (pintype "passive"))
    )
    (net (code "131") (name "unconnected-(P1-Pad40)") (class "Default")
      (node (ref "P1") (pin "40") (pinfunction "40_40") (pintype "passive"))
    )
    (net (code "132") (name "unconnected-(S1-C-Pad3)") (class "Default")
      (node (ref "S1") (pin "3") (pinfunction "C_3") (pintype "passive"))
    )
    (net (code "133") (name "unconnected-(S1-N.C.-Pad1)") (class "Default")
      (node (ref "S1") (pin "1") (pinfunction "N.C._1") (pintype "passive"))
    )
    (net (code "134") (name "unconnected-(S1-N.C.-Pad6)") (class "Default")
      (node (ref "S1") (pin "6") (pinfunction "N.C._6") (pintype "passive"))
    )
    (net (code "135") (name "unconnected-(S1-N.O.-Pad2)") (class "Default")
      (node (ref "S1") (pin "2") (pinfunction "N.O._2") (pintype "passive"))
    )
    (net (code "136") (name "unconnected-(U1-DOUT1{slash}DIN4(B)-Pad39)") (class "Default")
      (node (ref "U1") (pin "39") (pinfunction "DOUT1/DIN4(B)_39") (pintype "passive"))
    )
    (net (code "137") (name "unconnected-(U1-DOUT2{slash}DIN3(B)-Pad38)") (class "Default")
      (node (ref "U1") (pin "38") (pinfunction "DOUT2/DIN3(B)_38") (pintype "passive"))
    )
    (net (code "138") (name "unconnected-(U1-DOUT3{slash}DIN2(B)-Pad37)") (class "Default")
      (node (ref "U1") (pin "37") (pinfunction "DOUT3/DIN2(B)_37") (pintype "passive"))
    )
    (net (code "139") (name "unconnected-(U1-DOUT4{slash}DIN1(B)-Pad36)") (class "Default")
      (node (ref "U1") (pin "36") (pinfunction "DOUT4/DIN1(B)_36") (pintype "passive"))
    )
    (net (code "140") (name "unconnected-(U1-HVOUT61{slash}4-Pad44)") (class "Default")
      (node (ref "U1") (pin "44") (pinfunction "HVOUT61/4_44") (pintype "passive"))
    )
    (net (code "141") (name "unconnected-(U1-HVOUT62{slash}3-Pad43)") (class "Default")
      (node (ref "U1") (pin "43") (pinfunction "HVOUT62/3_43") (pintype "passive"))
    )
    (net (code "142") (name "unconnected-(U1-HVOUT63{slash}2-Pad42)") (class "Default")
      (node (ref "U1") (pin "42") (pinfunction "HVOUT63/2_42") (pintype "passive"))
    )
    (net (code "143") (name "unconnected-(U1-HVOUT64{slash}1-Pad41)") (class "Default")
      (node (ref "U1") (pin "41") (pinfunction "HVOUT64/1_41") (pintype "passive"))
    )
    (net (code "144") (name "unconnected-(U2-32kHz-Pad1)") (class "Default")
      (node (ref "U2") (pin "1") (pinfunction "32kHz_1") (pintype "passive"))
    )
    (net (code "145") (name "unconnected-(U2-~{RST}-Pad4)") (class "Default")
      (node (ref "U2") (pin "4") (pinfunction "~{RST}_4") (pintype "passive"))
    )
    (net (code "146") (name "unconnected-(U5-ALERT-Pad3)") (class "Default")
      (node (ref "U5") (pin "3") (pinfunction "ALERT_3") (pintype "passive"))
    )
    (net (code "147") (name "unconnected-(U5-nRESET-Pad6)") (class "Default")
      (node (ref "U5") (pin "6") (pinfunction "nRESET_6") (pintype "passive"))
    )
  )
)
